# mr_radar_trolley.net
KiCad netlist of a schematic drawn in EAGLE
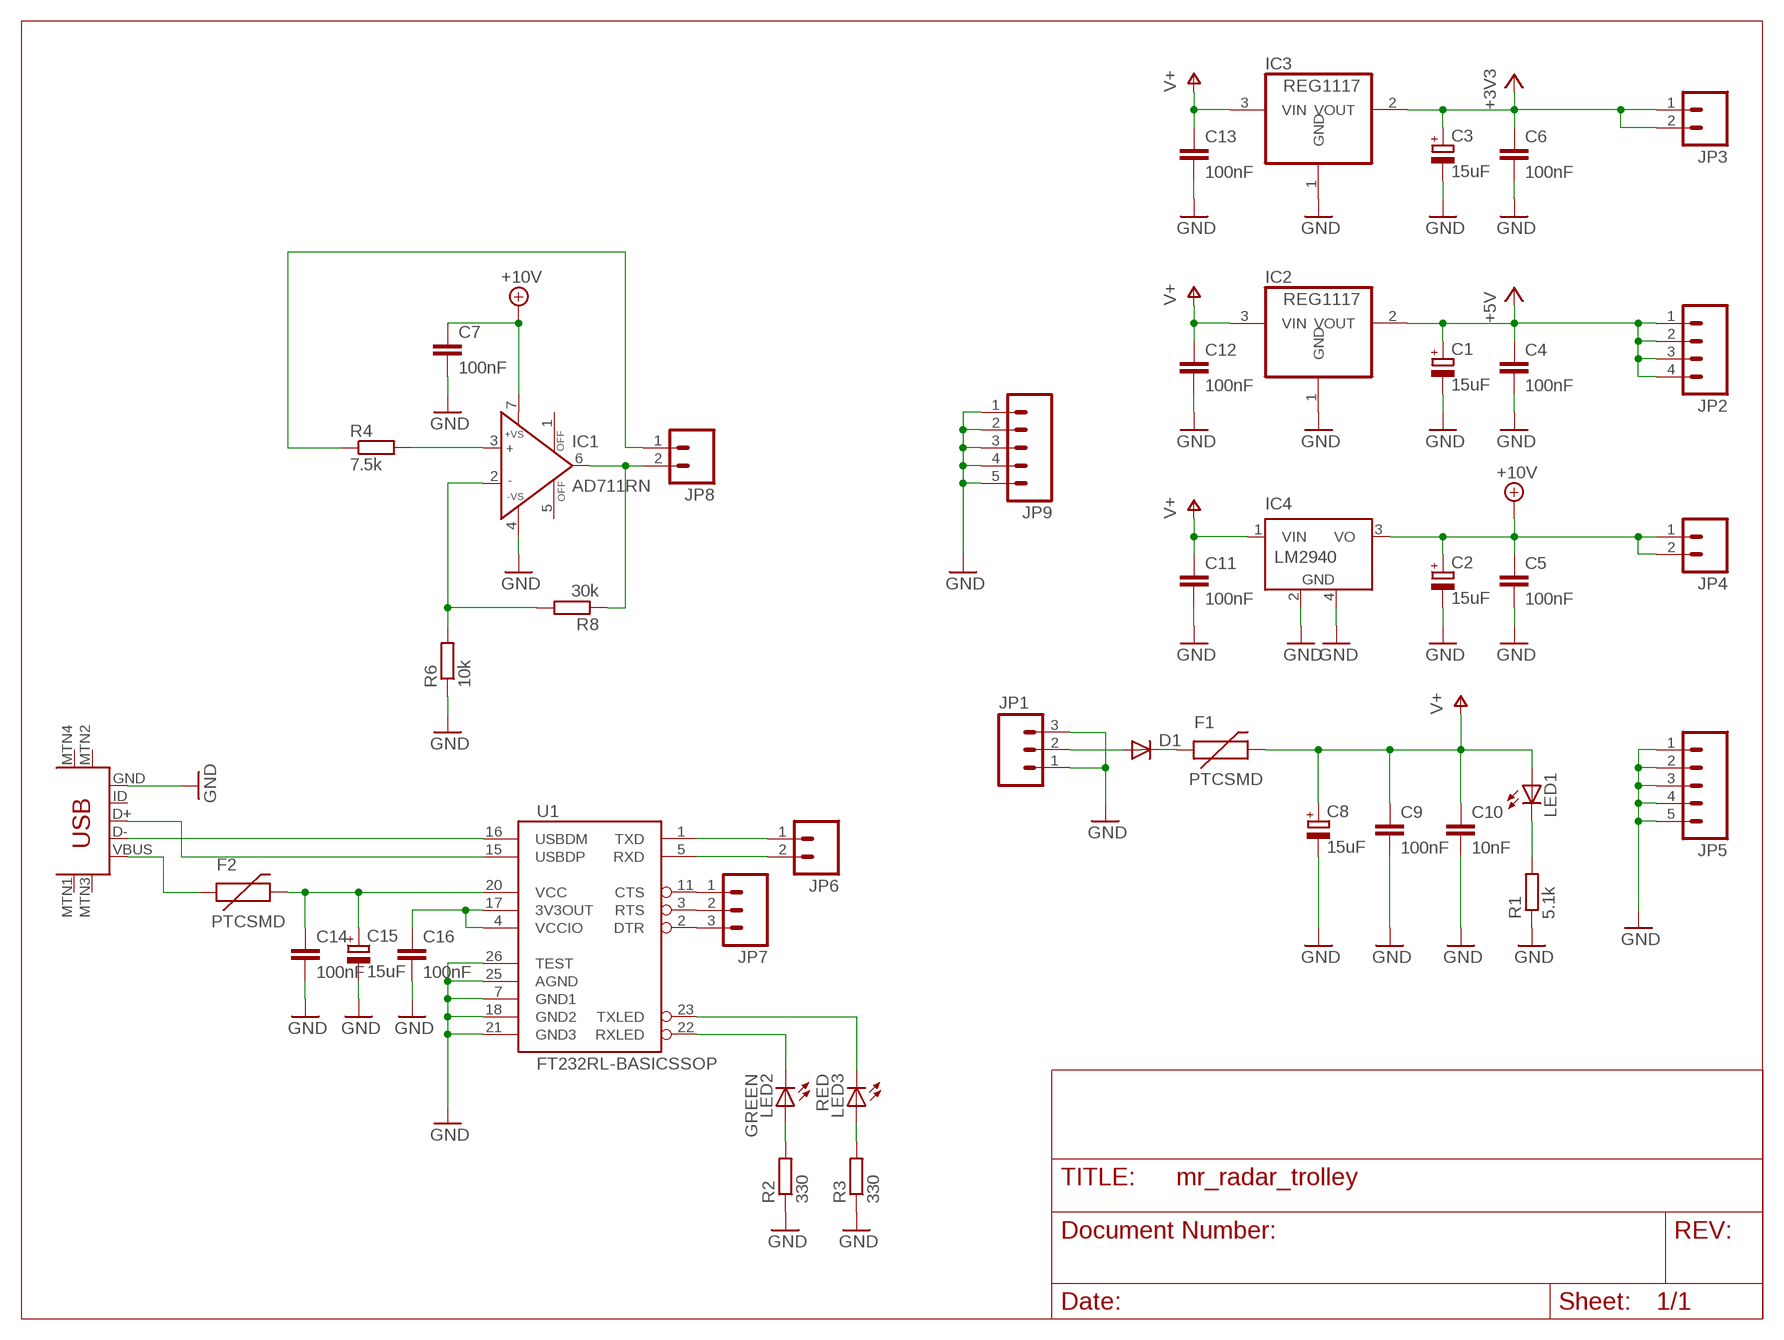
[diagram p0: schematic, sheet 1]

(export (version "E")
  (design (tool "Eeschema 10.0.6"))
  (components
    (comp (ref "C1")
      (value "15uF")
      (footprint "eagle-import:B_3528-21R")
      (libsource (lib "eagle-import") (part "CPOL-EUB/3528-21R"))
    )
    (comp (ref "C2")
      (value "15uF")
      (footprint "eagle-import:B_3528-21R")
      (libsource (lib "eagle-import") (part "CPOL-EUB/3528-21R"))
    )
    (comp (ref "C3")
      (value "15uF")
      (footprint "eagle-import:B_3528-21R")
      (libsource (lib "eagle-import") (part "CPOL-EUB/3528-21R"))
    )
    (comp (ref "C4")
      (value "100nF")
      (footprint "eagle-import:C0603")
      (libsource (lib "eagle-import") (part "C-EUC0603"))
    )
    (comp (ref "C5")
      (value "100nF")
      (footprint "eagle-import:C0603")
      (libsource (lib "eagle-import") (part "C-EUC0603"))
    )
    (comp (ref "C6")
      (value "100nF")
      (footprint "eagle-import:C0603")
      (libsource (lib "eagle-import") (part "C-EUC0603"))
    )
    (comp (ref "C7")
      (value "100nF")
      (footprint "eagle-import:C0603")
      (libsource (lib "eagle-import") (part "C-EUC0603"))
    )
    (comp (ref "C8")
      (value "15uF")
      (footprint "eagle-import:B_3528-21R")
      (libsource (lib "eagle-import") (part "CPOL-EUB/3528-21R"))
    )
    (comp (ref "C9")
      (value "100nF")
      (footprint "eagle-import:C0603")
      (libsource (lib "eagle-import") (part "C-EUC0603"))
    )
    (comp (ref "C10")
      (value "10nF")
      (footprint "eagle-import:C0603")
      (libsource (lib "eagle-import") (part "C-EUC0603"))
    )
    (comp (ref "C11")
      (value "100nF")
      (footprint "eagle-import:C0603")
      (libsource (lib "eagle-import") (part "C-EUC0603"))
    )
    (comp (ref "C12")
      (value "100nF")
      (footprint "eagle-import:C0603")
      (libsource (lib "eagle-import") (part "C-EUC0603"))
    )
    (comp (ref "C13")
      (value "100nF")
      (footprint "eagle-import:C0603")
      (libsource (lib "eagle-import") (part "C-EUC0603"))
    )
    (comp (ref "C14")
      (value "100nF")
      (footprint "eagle-import:C0603")
      (libsource (lib "eagle-import") (part "C-EUC0603"))
    )
    (comp (ref "C15")
      (value "15uF")
      (footprint "eagle-import:B_3528-21R")
      (libsource (lib "eagle-import") (part "CPOL-EUB/3528-21R"))
    )
    (comp (ref "C16")
      (value "100nF")
      (footprint "eagle-import:C0603")
      (libsource (lib "eagle-import") (part "C-EUC0603"))
    )
    (comp (ref "D1")
      (value "DIODE-SMC")
      (footprint "eagle-import:SMC")
      (libsource (lib "eagle-import") (part "DIODE-SMC"))
    )
    (comp (ref "F1")
      (value "PTCSMD")
      (footprint "eagle-import:PTC-1206")
      (libsource (lib "eagle-import") (part "PTCSMD"))
    )
    (comp (ref "F2")
      (value "PTCSMD")
      (footprint "eagle-import:PTC-1206")
      (libsource (lib "eagle-import") (part "PTCSMD"))
    )
    (comp (ref "IC1")
      (value "AD711RN")
      (footprint "eagle-import:SO8")
      (fields (field (name "MF") "ALTERA CORPORATION") (field (name "MPN") "AD711KRZ"))
      (libsource (lib "eagle-import") (part "AD711RN"))
    )
    (comp (ref "IC2")
      (value "REG1117")
      (footprint "eagle-import:SOT223")
      (libsource (lib "eagle-import") (part "REG1117"))
    )
    (comp (ref "IC3")
      (value "REG1117")
      (footprint "eagle-import:SOT223")
      (libsource (lib "eagle-import") (part "REG1117"))
    )
    (comp (ref "IC4")
      (value "LM2940")
      (footprint "eagle-import:SOT223")
      (fields (field (name "MF") "NATIONAL SEMICONDUCTOR") (field (name "MPN") "LM2936MP-5.0/NOPB"))
      (libsource (lib "eagle-import") (part "LM2936MP?-5.0"))
    )
    (comp (ref "JP1")
      (value "M03SCREW")
      (footprint "eagle-import:SCREWTERMINAL-3.5MM-3")
      (libsource (lib "eagle-import") (part "M03SCREW"))
    )
    (comp (ref "JP2")
      (value "M04LOCK")
      (footprint "eagle-import:1X04_LOCK")
      (libsource (lib "eagle-import") (part "M04LOCK"))
    )
    (comp (ref "JP3")
      (value "M02PTH")
      (footprint "eagle-import:1X02")
      (libsource (lib "eagle-import") (part "M02PTH"))
    )
    (comp (ref "JP4")
      (value "M02PTH")
      (footprint "eagle-import:1X02")
      (libsource (lib "eagle-import") (part "M02PTH"))
    )
    (comp (ref "JP5")
      (value "M05LOCK")
      (footprint "eagle-import:1X05_LOCK")
      (libsource (lib "eagle-import") (part "M05LOCK"))
    )
    (comp (ref "JP6")
      (value "M02PTH")
      (footprint "eagle-import:1X02")
      (libsource (lib "eagle-import") (part "M02PTH"))
    )
    (comp (ref "JP7")
      (value "M03PTH")
      (footprint "eagle-import:1X03")
      (libsource (lib "eagle-import") (part "M03PTH"))
    )
    (comp (ref "JP8")
      (value "M02PTH")
      (footprint "eagle-import:1X02")
      (libsource (lib "eagle-import") (part "M02PTH"))
    )
    (comp (ref "JP9")
      (value "M05LOCK")
      (footprint "eagle-import:1X05_LOCK")
      (libsource (lib "eagle-import") (part "M05LOCK"))
    )
    (comp (ref "LED1")
      (value "LEDCHIPLED_1206")
      (footprint "eagle-import:CHIPLED_1206")
      (libsource (lib "eagle-import") (part "LEDCHIPLED_1206"))
    )
    (comp (ref "LED2")
      (value "GREEN")
      (footprint "eagle-import:CHIPLED_1206")
      (libsource (lib "eagle-import") (part "LEDCHIPLED_1206"))
    )
    (comp (ref "LED3")
      (value "RED")
      (footprint "eagle-import:CHIPLED_1206")
      (libsource (lib "eagle-import") (part "LEDCHIPLED_1206"))
    )
    (comp (ref "R1")
      (value "5.1k")
      (footprint "eagle-import:R0603")
      (libsource (lib "eagle-import") (part "R-EU_R0603"))
    )
    (comp (ref "R2")
      (value "330")
      (footprint "eagle-import:M0805")
      (libsource (lib "eagle-import") (part "resistor_R-EU_M0805"))
    )
    (comp (ref "R3")
      (value "330")
      (footprint "eagle-import:M0805")
      (libsource (lib "eagle-import") (part "resistor_R-EU_M0805"))
    )
    (comp (ref "R4")
      (value "7.5k")
      (footprint "eagle-import:R0603")
      (libsource (lib "eagle-import") (part "R-EU_R0603"))
    )
    (comp (ref "R6")
      (value "10k")
      (footprint "eagle-import:R0603")
      (libsource (lib "eagle-import") (part "R-EU_R0603"))
    )
    (comp (ref "R8")
      (value "30k")
      (footprint "eagle-import:R0603")
      (libsource (lib "eagle-import") (part "R-EU_R0603"))
    )
    (comp (ref "U$1")
      (value "USB-MINIB-5PIN")
      (footprint "eagle-import:USB-MINIB")
      (libsource (lib "eagle-import") (part "USB-MINIB-5PIN"))
    )
    (comp (ref "U1")
      (value "FT232RL-BASICSSOP")
      (footprint "eagle-import:SSOP28DB")
      (libsource (lib "eagle-import") (part "FT232RL-BASICSSOP"))
    )
  )
  (nets
    (net (code "1") (name "+3V3") (class "Default")
      (node (ref "C3") (pin "+") (pinfunction "+_+") (pintype "passive"))
      (node (ref "C6") (pin "1") (pinfunction "1_1") (pintype "passive"))
      (node (ref "IC3") (pin "2") (pinfunction "VOUT_2") (pintype "output"))
      (node (ref "JP3") (pin "1") (pinfunction "1_1") (pintype "passive"))
      (node (ref "JP3") (pin "2") (pinfunction "2_2") (pintype "passive"))
    )
    (net (code "2") (name "+5V") (class "Default")
      (node (ref "C1") (pin "+") (pinfunction "+_+") (pintype "passive"))
      (node (ref "C4") (pin "1") (pinfunction "1_1") (pintype "passive"))
      (node (ref "IC2") (pin "2") (pinfunction "VOUT_2") (pintype "output"))
      (node (ref "JP2") (pin "1") (pinfunction "1_1") (pintype "passive"))
      (node (ref "JP2") (pin "2") (pinfunction "2_2") (pintype "passive"))
      (node (ref "JP2") (pin "3") (pinfunction "3_3") (pintype "passive"))
      (node (ref "JP2") (pin "4") (pinfunction "4_4") (pintype "passive"))
    )
    (net (code "3") (name "+10V") (class "Default")
      (node (ref "C2") (pin "+") (pinfunction "+_+") (pintype "passive"))
      (node (ref "C5") (pin "1") (pinfunction "1_1") (pintype "passive"))
      (node (ref "C7") (pin "1") (pinfunction "1_1") (pintype "passive"))
      (node (ref "IC1") (pin "7") (pinfunction "+VS_7") (pintype "input"))
      (node (ref "IC4") (pin "3") (pinfunction "VO_3") (pintype "passive"))
      (node (ref "JP4") (pin "1") (pinfunction "1_1") (pintype "passive"))
      (node (ref "JP4") (pin "2") (pinfunction "2_2") (pintype "passive"))
    )
    (net (code "4") (name "GND") (class "Default")
      (node (ref "C1") (pin "-") (pinfunction "-_-") (pintype "passive"))
      (node (ref "C10") (pin "2") (pinfunction "2_2") (pintype "passive"))
      (node (ref "C11") (pin "2") (pinfunction "2_2") (pintype "passive"))
      (node (ref "C12") (pin "2") (pinfunction "2_2") (pintype "passive"))
      (node (ref "C13") (pin "2") (pinfunction "2_2") (pintype "passive"))
      (node (ref "C14") (pin "2") (pinfunction "2_2") (pintype "passive"))
      (node (ref "C15") (pin "-") (pinfunction "-_-") (pintype "passive"))
      (node (ref "C16") (pin "2") (pinfunction "2_2") (pintype "passive"))
      (node (ref "C2") (pin "-") (pinfunction "-_-") (pintype "passive"))
      (node (ref "C3") (pin "-") (pinfunction "-_-") (pintype "passive"))
      (node (ref "C4") (pin "2") (pinfunction "2_2") (pintype "passive"))
      (node (ref "C5") (pin "2") (pinfunction "2_2") (pintype "passive"))
      (node (ref "C6") (pin "2") (pinfunction "2_2") (pintype "passive"))
      (node (ref "C7") (pin "2") (pinfunction "2_2") (pintype "passive"))
      (node (ref "C8") (pin "-") (pinfunction "-_-") (pintype "passive"))
      (node (ref "C9") (pin "2") (pinfunction "2_2") (pintype "passive"))
      (node (ref "IC1") (pin "4") (pinfunction "-VS_4") (pintype "input"))
      (node (ref "IC2") (pin "1") (pinfunction "GND_1") (pintype "power_in"))
      (node (ref "IC3") (pin "1") (pinfunction "GND_1") (pintype "power_in"))
      (node (ref "IC4") (pin "2") (pinfunction "GND_2") (pintype "passive"))
      (node (ref "IC4") (pin "4") (pinfunction "GND_4") (pintype "passive"))
      (node (ref "JP1") (pin "1") (pinfunction "1_1") (pintype "passive"))
      (node (ref "JP1") (pin "3") (pinfunction "3_3") (pintype "passive"))
      (node (ref "JP5") (pin "1") (pinfunction "1_1") (pintype "passive"))
      (node (ref "JP5") (pin "2") (pinfunction "2_2") (pintype "passive"))
      (node (ref "JP5") (pin "3") (pinfunction "3_3") (pintype "passive"))
      (node (ref "JP5") (pin "4") (pinfunction "4_4") (pintype "passive"))
      (node (ref "JP5") (pin "5") (pinfunction "5_5") (pintype "passive"))
      (node (ref "JP9") (pin "1") (pinfunction "1_1") (pintype "passive"))
      (node (ref "JP9") (pin "2") (pinfunction "2_2") (pintype "passive"))
      (node (ref "JP9") (pin "3") (pinfunction "3_3") (pintype "passive"))
      (node (ref "JP9") (pin "4") (pinfunction "4_4") (pintype "passive"))
      (node (ref "JP9") (pin "5") (pinfunction "5_5") (pintype "passive"))
      (node (ref "R1") (pin "1") (pinfunction "1_1") (pintype "passive"))
      (node (ref "R2") (pin "1") (pinfunction "1_1") (pintype "passive"))
      (node (ref "R3") (pin "1") (pinfunction "1_1") (pintype "passive"))
      (node (ref "R6") (pin "1") (pinfunction "1_1") (pintype "passive"))
      (node (ref "U$1") (pin "GND") (pinfunction "GND_GND") (pintype "bidirectional"))
      (node (ref "U1") (pin "18") (pinfunction "GND2_18") (pintype "power_in"))
      (node (ref "U1") (pin "21") (pinfunction "GND3_21") (pintype "power_in"))
      (node (ref "U1") (pin "25") (pinfunction "AGND_25") (pintype "power_in"))
      (node (ref "U1") (pin "26") (pinfunction "TEST_26") (pintype "input"))
      (node (ref "U1") (pin "7") (pinfunction "GND1_7") (pintype "power_in"))
    )
    (net (code "5") (name "Net-(D1-PadA)") (class "Default")
      (node (ref "D1") (pin "A") (pinfunction "A_A") (pintype "passive"))
      (node (ref "JP1") (pin "2") (pinfunction "2_2") (pintype "passive"))
    )
    (net (code "6") (name "Net-(D1-PadC)") (class "Default")
      (node (ref "D1") (pin "C") (pinfunction "C_C") (pintype "passive"))
      (node (ref "F1") (pin "1") (pinfunction "1_1") (pintype "bidirectional"))
    )
    (net (code "7") (name "Net-(F2-Pad1)") (class "Default")
      (node (ref "F2") (pin "1") (pinfunction "1_1") (pintype "bidirectional"))
      (node (ref "U$1") (pin "VBUS") (pinfunction "VBUS_VBUS") (pintype "bidirectional"))
    )
    (net (code "8") (name "Net-(IC1-IN+)") (class "Default")
      (node (ref "IC1") (pin "3") (pinfunction "IN+_3") (pintype "input"))
      (node (ref "R4") (pin "2") (pinfunction "2_2") (pintype "passive"))
    )
    (net (code "9") (name "Net-(IC1-IN-)") (class "Default")
      (node (ref "IC1") (pin "2") (pinfunction "IN-_2") (pintype "input"))
      (node (ref "R6") (pin "2") (pinfunction "2_2") (pintype "passive"))
      (node (ref "R8") (pin "2") (pinfunction "2_2") (pintype "passive"))
    )
    (net (code "10") (name "Net-(IC1-OUT)") (class "Default")
      (node (ref "IC1") (pin "6") (pinfunction "OUT_6") (pintype "output"))
      (node (ref "JP8") (pin "2") (pinfunction "2_2") (pintype "passive"))
      (node (ref "R8") (pin "1") (pinfunction "1_1") (pintype "passive"))
    )
    (net (code "11") (name "Net-(JP8-Pad1)") (class "Default")
      (node (ref "JP8") (pin "1") (pinfunction "1_1") (pintype "passive"))
      (node (ref "R4") (pin "1") (pinfunction "1_1") (pintype "passive"))
    )
    (net (code "12") (name "Net-(LED1-PadC)") (class "Default")
      (node (ref "LED1") (pin "C") (pinfunction "C_C") (pintype "passive"))
      (node (ref "R1") (pin "2") (pinfunction "2_2") (pintype "passive"))
    )
    (net (code "13") (name "Net-(LED2-PadA)") (class "Default")
      (node (ref "LED2") (pin "A") (pinfunction "A_A") (pintype "passive"))
      (node (ref "R2") (pin "2") (pinfunction "2_2") (pintype "passive"))
    )
    (net (code "14") (name "Net-(LED3-PadA)") (class "Default")
      (node (ref "LED3") (pin "A") (pinfunction "A_A") (pintype "passive"))
      (node (ref "R3") (pin "2") (pinfunction "2_2") (pintype "passive"))
    )
    (net (code "15") (name "Net-(U1-3V3OUT)") (class "Default")
      (node (ref "C16") (pin "1") (pinfunction "1_1") (pintype "passive"))
      (node (ref "U1") (pin "17") (pinfunction "3V3OUT_17") (pintype "output"))
      (node (ref "U1") (pin "4") (pinfunction "VCCIO_4") (pintype "power_in"))
    )
    (net (code "16") (name "Net-(U1-CTS)") (class "Default")
      (node (ref "JP7") (pin "1") (pinfunction "1_1") (pintype "passive"))
      (node (ref "U1") (pin "11") (pinfunction "CTS_11") (pintype "bidirectional"))
    )
    (net (code "17") (name "Net-(U1-DTR)") (class "Default")
      (node (ref "JP7") (pin "3") (pinfunction "3_3") (pintype "passive"))
      (node (ref "U1") (pin "2") (pinfunction "DTR_2") (pintype "bidirectional"))
    )
    (net (code "18") (name "Net-(U1-RTS)") (class "Default")
      (node (ref "JP7") (pin "2") (pinfunction "2_2") (pintype "passive"))
      (node (ref "U1") (pin "3") (pinfunction "RTS_3") (pintype "bidirectional"))
    )
    (net (code "19") (name "Net-(U1-RXD)") (class "Default")
      (node (ref "JP6") (pin "2") (pinfunction "2_2") (pintype "passive"))
      (node (ref "U1") (pin "5") (pinfunction "RXD_5") (pintype "input"))
    )
    (net (code "20") (name "Net-(U1-RXLED)") (class "Default")
      (node (ref "LED2") (pin "C") (pinfunction "C_C") (pintype "passive"))
      (node (ref "U1") (pin "22") (pinfunction "RXLED_22") (pintype "bidirectional"))
    )
    (net (code "21") (name "Net-(U1-TXD)") (class "Default")
      (node (ref "JP6") (pin "1") (pinfunction "1_1") (pintype "passive"))
      (node (ref "U1") (pin "1") (pinfunction "TXD_1") (pintype "output"))
    )
    (net (code "22") (name "Net-(U1-TXLED)") (class "Default")
      (node (ref "LED3") (pin "C") (pinfunction "C_C") (pintype "passive"))
      (node (ref "U1") (pin "23") (pinfunction "TXLED_23") (pintype "bidirectional"))
    )
    (net (code "23") (name "Net-(U1-USBDM)") (class "Default")
      (node (ref "U$1") (pin "D-") (pinfunction "D-_D-") (pintype "bidirectional"))
      (node (ref "U1") (pin "16") (pinfunction "USBDM_16") (pintype "bidirectional"))
    )
    (net (code "24") (name "Net-(U1-USBDP)") (class "Default")
      (node (ref "U$1") (pin "D+") (pinfunction "D+_D+") (pintype "bidirectional"))
      (node (ref "U1") (pin "15") (pinfunction "USBDP_15") (pintype "bidirectional"))
    )
    (net (code "25") (name "Net-(U1-VCC)") (class "Default")
      (node (ref "C14") (pin "1") (pinfunction "1_1") (pintype "passive"))
      (node (ref "C15") (pin "+") (pinfunction "+_+") (pintype "passive"))
      (node (ref "F2") (pin "2") (pinfunction "2_2") (pintype "bidirectional"))
      (node (ref "U1") (pin "20") (pinfunction "VCC_20") (pintype "power_in"))
    )
    (net (code "26") (name "V+") (class "Default")
      (node (ref "C10") (pin "1") (pinfunction "1_1") (pintype "passive"))
      (node (ref "C11") (pin "1") (pinfunction "1_1") (pintype "passive"))
      (node (ref "C12") (pin "1") (pinfunction "1_1") (pintype "passive"))
      (node (ref "C13") (pin "1") (pinfunction "1_1") (pintype "passive"))
      (node (ref "C8") (pin "+") (pinfunction "+_+") (pintype "passive"))
      (node (ref "C9") (pin "1") (pinfunction "1_1") (pintype "passive"))
      (node (ref "F1") (pin "2") (pinfunction "2_2") (pintype "bidirectional"))
      (node (ref "IC2") (pin "3") (pinfunction "VIN_3") (pintype "input"))
      (node (ref "IC3") (pin "3") (pinfunction "VIN_3") (pintype "input"))
      (node (ref "IC4") (pin "1") (pinfunction "VIN_1") (pintype "input"))
      (node (ref "LED1") (pin "A") (pinfunction "A_A") (pintype "passive"))
    )
    (net (code "27") (name "unconnected-(IC1-OFF-Pad1)") (class "Default")
      (node (ref "IC1") (pin "1") (pinfunction "OFF_1") (pintype "passive"))
    )
    (net (code "28") (name "unconnected-(IC1-OFF-Pad5)") (class "Default")
      (node (ref "IC1") (pin "5") (pinfunction "OFF_5") (pintype "passive"))
    )
    (net (code "29") (name "unconnected-(U$1-MTN1-PadMTN3)") (class "Default")
      (node (ref "U$1") (pin "MTN3") (pinfunction "MTN1_MTN3") (pintype "bidirectional"))
    )
    (net (code "30") (name "unconnected-(U$1-MTN2-PadMTN1)") (class "Default")
      (node (ref "U$1") (pin "MTN1") (pinfunction "MTN2_MTN1") (pintype "bidirectional"))
    )
    (net (code "31") (name "unconnected-(U$1-MTN3-PadMTN2)") (class "Default")
      (node (ref "U$1") (pin "MTN2") (pinfunction "MTN3_MTN2") (pintype "bidirectional"))
    )
    (net (code "32") (name "unconnected-(U$1-PadID)") (class "Default")
      (node (ref "U$1") (pin "ID") (pinfunction "ID_ID") (pintype "bidirectional"))
    )
    (net (code "33") (name "unconnected-(U$1-PadMTN4)") (class "Default")
      (node (ref "U$1") (pin "MTN4") (pinfunction "MTN4_MTN4") (pintype "bidirectional"))
    )
  )
)
